# v1_4_button.net
KiCad netlist of a schematic drawn in EAGLE
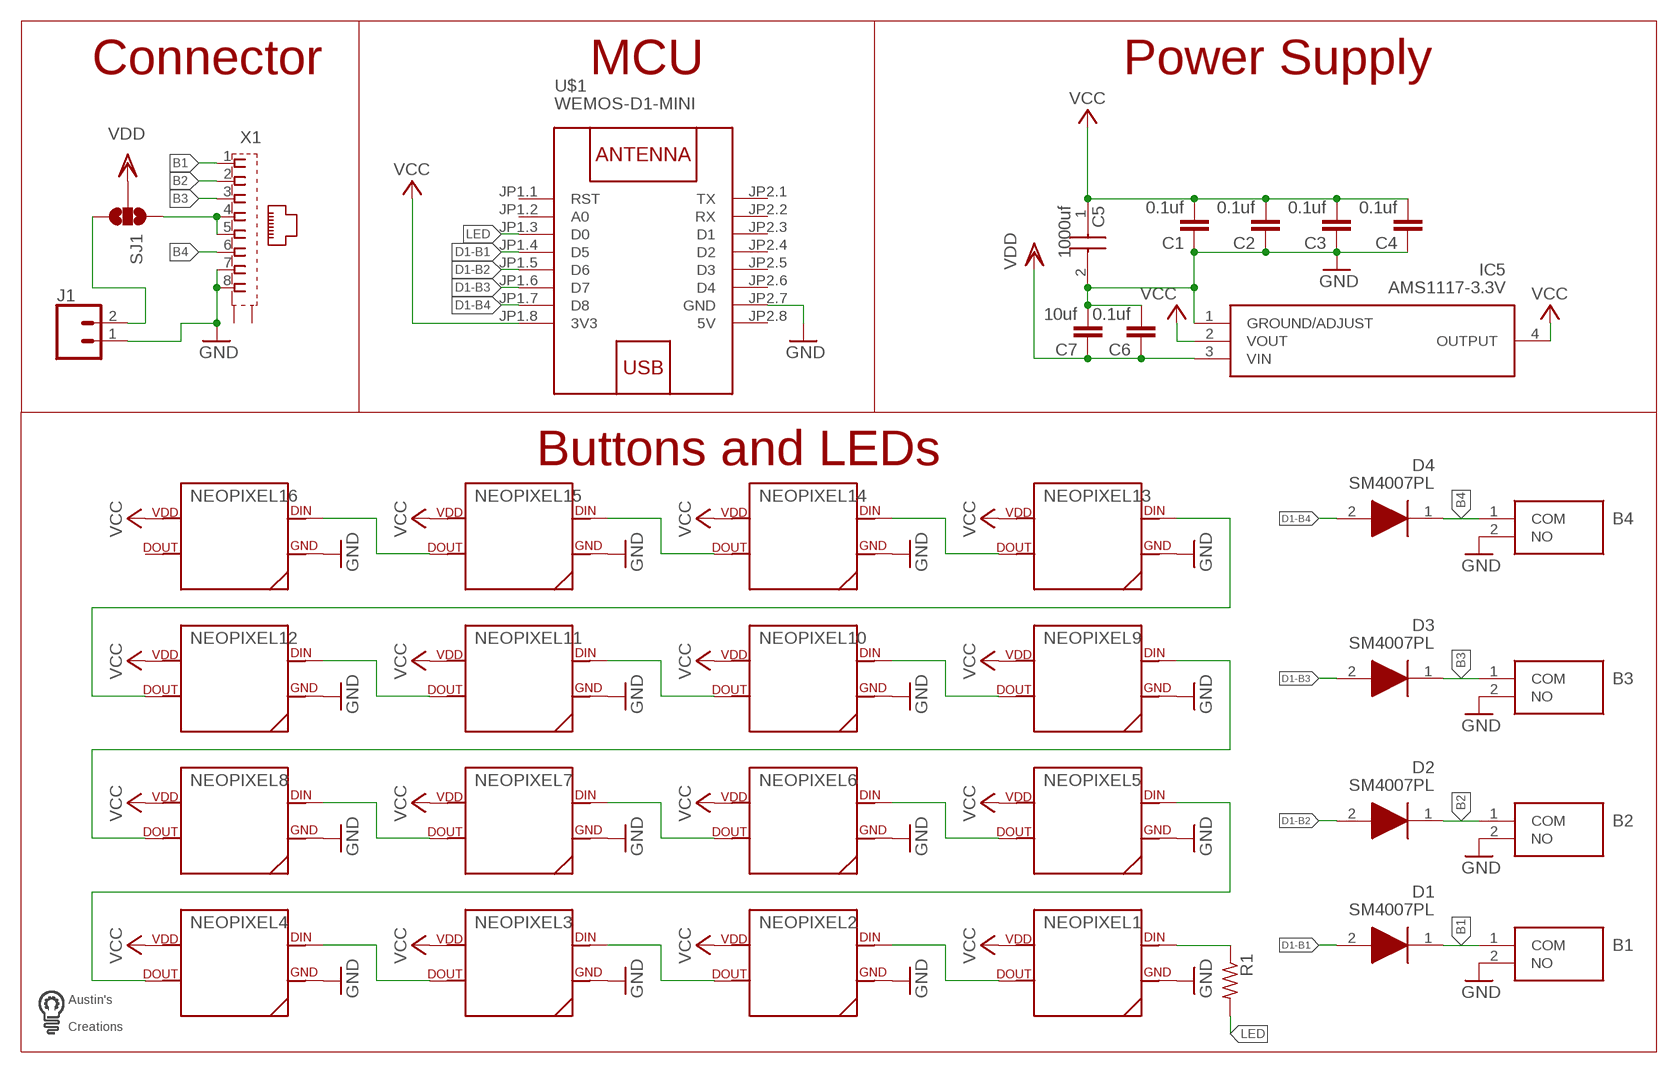
[diagram p0: schematic, sheet 1]

(export (version "E")
  (design (tool "Eeschema 10.0.6"))
  (components
    (comp (ref "B1")
      (value "PTS636_SM25F_SMTR_LFS")
      (footprint "eagle-import:PTS636SM25FSMTRLFS")
      (fields
        (field (name "ARROW_PART_NUMBER") "PTS636 SM25F SMTR LFS")
        (field (name "MOUSER_PART_NUMBER") "611-PTS636SM25FSMTRL")
      )
      (libsource (lib "eagle-import") (part "PTS636_SM25F_SMTR_LFS"))
    )
    (comp (ref "B2")
      (value "PTS636_SM25F_SMTR_LFS")
      (footprint "eagle-import:PTS636SM25FSMTRLFS")
      (fields
        (field (name "ARROW_PART_NUMBER") "PTS636 SM25F SMTR LFS")
        (field (name "MOUSER_PART_NUMBER") "611-PTS636SM25FSMTRL")
      )
      (libsource (lib "eagle-import") (part "PTS636_SM25F_SMTR_LFS"))
    )
    (comp (ref "B3")
      (value "PTS636_SM25F_SMTR_LFS")
      (footprint "eagle-import:PTS636SM25FSMTRLFS")
      (fields
        (field (name "ARROW_PART_NUMBER") "PTS636 SM25F SMTR LFS")
        (field (name "MOUSER_PART_NUMBER") "611-PTS636SM25FSMTRL")
      )
      (libsource (lib "eagle-import") (part "PTS636_SM25F_SMTR_LFS"))
    )
    (comp (ref "B4")
      (value "PTS636_SM25F_SMTR_LFS")
      (footprint "eagle-import:PTS636SM25FSMTRLFS")
      (fields
        (field (name "ARROW_PART_NUMBER") "PTS636 SM25F SMTR LFS")
        (field (name "MOUSER_PART_NUMBER") "611-PTS636SM25FSMTRL")
      )
      (libsource (lib "eagle-import") (part "PTS636_SM25F_SMTR_LFS"))
    )
    (comp (ref "C1")
      (value "0.1uf")
      (footprint "eagle-import:C0603")
      (libsource (lib "eagle-import") (part "C-EUC0603"))
    )
    (comp (ref "C2")
      (value "0.1uf")
      (footprint "eagle-import:C0603")
      (libsource (lib "eagle-import") (part "C-EUC0603"))
    )
    (comp (ref "C3")
      (value "0.1uf")
      (footprint "eagle-import:C0603")
      (libsource (lib "eagle-import") (part "C-EUC0603"))
    )
    (comp (ref "C4")
      (value "0.1uf")
      (footprint "eagle-import:C0603")
      (libsource (lib "eagle-import") (part "C-EUC0603"))
    )
    (comp (ref "C5")
      (value "1000uf")
      (footprint "eagle-import:CAPAE1030X1050N")
      (fields
        (field (name "MANUFACTURER_PART_NUMBER") "EEE-0JA102P")
        (field (name "MOUSER_PART_NUMBER") "667-EEE-0JA102P")
      )
      (libsource (lib "eagle-import") (part "EEE-0JA102P"))
    )
    (comp (ref "C6")
      (value "0.1uf")
      (footprint "eagle-import:C0603")
      (libsource (lib "eagle-import") (part "C-EUC0603"))
    )
    (comp (ref "C7")
      (value "10uf")
      (footprint "eagle-import:C0603")
      (libsource (lib "eagle-import") (part "C-EUC0603"))
    )
    (comp (ref "D1")
      (value "SM4007PL")
      (footprint "eagle-import:SODFL3718X125N")
      (libsource (lib "eagle-import") (part "SM4007PL"))
    )
    (comp (ref "D2")
      (value "SM4007PL")
      (footprint "eagle-import:SODFL3718X125N")
      (libsource (lib "eagle-import") (part "SM4007PL"))
    )
    (comp (ref "D3")
      (value "SM4007PL")
      (footprint "eagle-import:SODFL3718X125N")
      (libsource (lib "eagle-import") (part "SM4007PL"))
    )
    (comp (ref "D4")
      (value "SM4007PL")
      (footprint "eagle-import:SODFL3718X125N")
      (libsource (lib "eagle-import") (part "SM4007PL"))
    )
    (comp (ref "IC5")
      (value "AMS1117-3.3V")
      (footprint "eagle-import:SOT229P700X180-4N")
      (fields (field (name "MANUFACTURER_PART_NUMBER") "ams1117-3.3v"))
      (libsource (lib "eagle-import") (part "AMS1117-3.3V"))
    )
    (comp (ref "J1")
      (value "CONN_025MM")
      (footprint "eagle-import:SCREWTERMINAL-5MM-2")
      (libsource (lib "eagle-import") (part "CONN_025MM"))
    )
    (comp (ref "NEOPIXEL1")
      (value "SK6812NEOPIXEL5050")
      (footprint "eagle-import:SK6812")
      (libsource (lib "eagle-import") (part "SK68125050NEOPIXEL"))
    )
    (comp (ref "NEOPIXEL2")
      (value "SK6812NEOPIXEL5050")
      (footprint "eagle-import:SK6812")
      (libsource (lib "eagle-import") (part "SK68125050NEOPIXEL"))
    )
    (comp (ref "NEOPIXEL3")
      (value "SK6812NEOPIXEL5050")
      (footprint "eagle-import:SK6812")
      (libsource (lib "eagle-import") (part "SK68125050NEOPIXEL"))
    )
    (comp (ref "NEOPIXEL4")
      (value "SK6812NEOPIXEL5050")
      (footprint "eagle-import:SK6812")
      (libsource (lib "eagle-import") (part "SK68125050NEOPIXEL"))
    )
    (comp (ref "NEOPIXEL5")
      (value "SK6812NEOPIXEL5050")
      (footprint "eagle-import:SK6812")
      (libsource (lib "eagle-import") (part "SK68125050NEOPIXEL"))
    )
    (comp (ref "NEOPIXEL6")
      (value "SK6812NEOPIXEL5050")
      (footprint "eagle-import:SK6812")
      (libsource (lib "eagle-import") (part "SK68125050NEOPIXEL"))
    )
    (comp (ref "NEOPIXEL7")
      (value "SK6812NEOPIXEL5050")
      (footprint "eagle-import:SK6812")
      (libsource (lib "eagle-import") (part "SK68125050NEOPIXEL"))
    )
    (comp (ref "NEOPIXEL8")
      (value "SK6812NEOPIXEL5050")
      (footprint "eagle-import:SK6812")
      (libsource (lib "eagle-import") (part "SK68125050NEOPIXEL"))
    )
    (comp (ref "NEOPIXEL9")
      (value "SK6812NEOPIXEL5050")
      (footprint "eagle-import:SK6812")
      (libsource (lib "eagle-import") (part "SK68125050NEOPIXEL"))
    )
    (comp (ref "NEOPIXEL10")
      (value "SK6812NEOPIXEL5050")
      (footprint "eagle-import:SK6812")
      (libsource (lib "eagle-import") (part "SK68125050NEOPIXEL"))
    )
    (comp (ref "NEOPIXEL11")
      (value "SK6812NEOPIXEL5050")
      (footprint "eagle-import:SK6812")
      (libsource (lib "eagle-import") (part "SK68125050NEOPIXEL"))
    )
    (comp (ref "NEOPIXEL12")
      (value "SK6812NEOPIXEL5050")
      (footprint "eagle-import:SK6812")
      (libsource (lib "eagle-import") (part "SK68125050NEOPIXEL"))
    )
    (comp (ref "NEOPIXEL13")
      (value "SK6812NEOPIXEL5050")
      (footprint "eagle-import:SK6812")
      (libsource (lib "eagle-import") (part "SK68125050NEOPIXEL"))
    )
    (comp (ref "NEOPIXEL14")
      (value "SK6812NEOPIXEL5050")
      (footprint "eagle-import:SK6812")
      (libsource (lib "eagle-import") (part "SK68125050NEOPIXEL"))
    )
    (comp (ref "NEOPIXEL15")
      (value "SK6812NEOPIXEL5050")
      (footprint "eagle-import:SK6812")
      (libsource (lib "eagle-import") (part "SK68125050NEOPIXEL"))
    )
    (comp (ref "NEOPIXEL16")
      (value "SK6812NEOPIXEL5050")
      (footprint "eagle-import:SK6812")
      (libsource (lib "eagle-import") (part "SK68125050NEOPIXEL"))
    )
    (comp (ref "R1")
      (value "R-US_R0603")
      (footprint "eagle-import:R0603")
      (libsource (lib "eagle-import") (part "R-US_R0603"))
    )
    (comp (ref "SJ1")
      (value "SOLDERJUMPER_2WAYPASTE1&2")
      (footprint "eagle-import:SJ_3_PASTE1&2")
      (libsource (lib "eagle-import") (part "SOLDERJUMPER_2WAYPASTE1&2"))
    )
    (comp (ref "U$1")
      (value "WEMOS-D1-MINI")
      (footprint "eagle-import:WEMOS-D1-MINI")
      (libsource (lib "eagle-import") (part "WEMOS-D1-MINI"))
    )
    (comp (ref "U$2")
      (value "LOGO")
      (footprint "eagle-import:LOGO")
      (libsource (lib "eagle-import") (part "LOGO"))
    )
    (comp (ref "X1")
      (value "0446200002")
      (footprint "eagle-import:0446200002")
      (fields (field (name "MF") "MOLEX"))
      (libsource (lib "eagle-import") (part "0446200002"))
    )
  )
  (nets
    (net (code "1") (name "/5V") (class "Default")
      (node (ref "U$1") (pin "JP2.8") (pinfunction "5V_JP2.8") (pintype "power_in"))
    )
    (net (code "2") (name "B1") (class "Default")
      (node (ref "B1") (pin "1") (pinfunction "COM_1") (pintype "bidirectional"))
      (node (ref "D1") (pin "1") (pinfunction "K_1") (pintype "bidirectional"))
      (node (ref "X1") (pin "1") (pinfunction "1_1") (pintype "passive"))
    )
    (net (code "3") (name "B2") (class "Default")
      (node (ref "B2") (pin "1") (pinfunction "COM_1") (pintype "bidirectional"))
      (node (ref "D2") (pin "1") (pinfunction "K_1") (pintype "bidirectional"))
      (node (ref "X1") (pin "2") (pinfunction "2_2") (pintype "passive"))
    )
    (net (code "4") (name "B3") (class "Default")
      (node (ref "B3") (pin "1") (pinfunction "COM_1") (pintype "bidirectional"))
      (node (ref "D3") (pin "1") (pinfunction "K_1") (pintype "bidirectional"))
      (node (ref "X1") (pin "3") (pinfunction "3_3") (pintype "passive"))
    )
    (net (code "5") (name "B4") (class "Default")
      (node (ref "B4") (pin "1") (pinfunction "COM_1") (pintype "bidirectional"))
      (node (ref "D4") (pin "1") (pinfunction "K_1") (pintype "bidirectional"))
      (node (ref "X1") (pin "6") (pinfunction "6_6") (pintype "passive"))
    )
    (net (code "6") (name "D1-B1") (class "Default")
      (node (ref "D1") (pin "2") (pinfunction "A_2") (pintype "bidirectional"))
      (node (ref "U$1") (pin "JP1.4") (pinfunction "D5_JP1.4") (pintype "bidirectional"))
    )
    (net (code "7") (name "D1-B2") (class "Default")
      (node (ref "D2") (pin "2") (pinfunction "A_2") (pintype "bidirectional"))
      (node (ref "U$1") (pin "JP1.5") (pinfunction "D6_JP1.5") (pintype "bidirectional"))
    )
    (net (code "8") (name "D1-B3") (class "Default")
      (node (ref "D3") (pin "2") (pinfunction "A_2") (pintype "bidirectional"))
      (node (ref "U$1") (pin "JP1.6") (pinfunction "D7_JP1.6") (pintype "bidirectional"))
    )
    (net (code "9") (name "D1-B4") (class "Default")
      (node (ref "D4") (pin "2") (pinfunction "A_2") (pintype "bidirectional"))
      (node (ref "U$1") (pin "JP1.7") (pinfunction "D8_JP1.7") (pintype "bidirectional"))
    )
    (net (code "10") (name "GND") (class "Default")
      (node (ref "B1") (pin "2") (pinfunction "NO_2") (pintype "bidirectional"))
      (node (ref "B2") (pin "2") (pinfunction "NO_2") (pintype "bidirectional"))
      (node (ref "B3") (pin "2") (pinfunction "NO_2") (pintype "bidirectional"))
      (node (ref "B4") (pin "2") (pinfunction "NO_2") (pintype "bidirectional"))
      (node (ref "C1") (pin "1") (pinfunction "1_1") (pintype "passive"))
      (node (ref "C2") (pin "1") (pinfunction "1_1") (pintype "passive"))
      (node (ref "C3") (pin "1") (pinfunction "1_1") (pintype "passive"))
      (node (ref "C4") (pin "1") (pinfunction "1_1") (pintype "passive"))
      (node (ref "C5") (pin "2") (pinfunction "-_2") (pintype "bidirectional"))
      (node (ref "C6") (pin "2") (pinfunction "2_2") (pintype "passive"))
      (node (ref "C7") (pin "2") (pinfunction "2_2") (pintype "passive"))
      (node (ref "IC5") (pin "1") (pinfunction "GROUND/ADJUST_1") (pintype "bidirectional"))
      (node (ref "J1") (pin "1") (pinfunction "1_1") (pintype "passive"))
      (node (ref "NEOPIXEL1") (pin "3") (pinfunction "GND_3") (pintype "bidirectional"))
      (node (ref "NEOPIXEL10") (pin "3") (pinfunction "GND_3") (pintype "bidirectional"))
      (node (ref "NEOPIXEL11") (pin "3") (pinfunction "GND_3") (pintype "bidirectional"))
      (node (ref "NEOPIXEL12") (pin "3") (pinfunction "GND_3") (pintype "bidirectional"))
      (node (ref "NEOPIXEL13") (pin "3") (pinfunction "GND_3") (pintype "bidirectional"))
      (node (ref "NEOPIXEL14") (pin "3") (pinfunction "GND_3") (pintype "bidirectional"))
      (node (ref "NEOPIXEL15") (pin "3") (pinfunction "GND_3") (pintype "bidirectional"))
      (node (ref "NEOPIXEL16") (pin "3") (pinfunction "GND_3") (pintype "bidirectional"))
      (node (ref "NEOPIXEL2") (pin "3") (pinfunction "GND_3") (pintype "bidirectional"))
      (node (ref "NEOPIXEL3") (pin "3") (pinfunction "GND_3") (pintype "bidirectional"))
      (node (ref "NEOPIXEL4") (pin "3") (pinfunction "GND_3") (pintype "bidirectional"))
      (node (ref "NEOPIXEL5") (pin "3") (pinfunction "GND_3") (pintype "bidirectional"))
      (node (ref "NEOPIXEL6") (pin "3") (pinfunction "GND_3") (pintype "bidirectional"))
      (node (ref "NEOPIXEL7") (pin "3") (pinfunction "GND_3") (pintype "bidirectional"))
      (node (ref "NEOPIXEL8") (pin "3") (pinfunction "GND_3") (pintype "bidirectional"))
      (node (ref "NEOPIXEL9") (pin "3") (pinfunction "GND_3") (pintype "bidirectional"))
      (node (ref "U$1") (pin "JP2.7") (pinfunction "GND_JP2.7") (pintype "power_in"))
      (node (ref "X1") (pin "7") (pinfunction "7_7") (pintype "passive"))
      (node (ref "X1") (pin "8") (pinfunction "8_8") (pintype "passive"))
    )
    (net (code "11") (name "LED") (class "Default")
      (node (ref "R1") (pin "2") (pinfunction "2_2") (pintype "passive"))
      (node (ref "U$1") (pin "JP1.3") (pinfunction "D0_JP1.3") (pintype "bidirectional"))
    )
    (net (code "12") (name "Net-(J1-Pad2)") (class "Default")
      (node (ref "J1") (pin "2") (pinfunction "2_2") (pintype "passive"))
      (node (ref "SJ1") (pin "3") (pinfunction "3_3") (pintype "passive"))
    )
    (net (code "13") (name "Net-(NEOPIXEL1-DIN)") (class "Default")
      (node (ref "NEOPIXEL1") (pin "4") (pinfunction "DIN_4") (pintype "bidirectional"))
      (node (ref "R1") (pin "1") (pinfunction "1_1") (pintype "passive"))
    )
    (net (code "14") (name "Net-(NEOPIXEL1-DOUT)") (class "Default")
      (node (ref "NEOPIXEL1") (pin "2") (pinfunction "DOUT_2") (pintype "bidirectional"))
      (node (ref "NEOPIXEL2") (pin "4") (pinfunction "DIN_4") (pintype "bidirectional"))
    )
    (net (code "15") (name "Net-(NEOPIXEL2-DOUT)") (class "Default")
      (node (ref "NEOPIXEL2") (pin "2") (pinfunction "DOUT_2") (pintype "bidirectional"))
      (node (ref "NEOPIXEL3") (pin "4") (pinfunction "DIN_4") (pintype "bidirectional"))
    )
    (net (code "16") (name "Net-(NEOPIXEL3-DOUT)") (class "Default")
      (node (ref "NEOPIXEL3") (pin "2") (pinfunction "DOUT_2") (pintype "bidirectional"))
      (node (ref "NEOPIXEL4") (pin "4") (pinfunction "DIN_4") (pintype "bidirectional"))
    )
    (net (code "17") (name "Net-(NEOPIXEL4-DOUT)") (class "Default")
      (node (ref "NEOPIXEL4") (pin "2") (pinfunction "DOUT_2") (pintype "bidirectional"))
      (node (ref "NEOPIXEL5") (pin "4") (pinfunction "DIN_4") (pintype "bidirectional"))
    )
    (net (code "18") (name "Net-(NEOPIXEL5-DOUT)") (class "Default")
      (node (ref "NEOPIXEL5") (pin "2") (pinfunction "DOUT_2") (pintype "bidirectional"))
      (node (ref "NEOPIXEL6") (pin "4") (pinfunction "DIN_4") (pintype "bidirectional"))
    )
    (net (code "19") (name "Net-(NEOPIXEL6-DOUT)") (class "Default")
      (node (ref "NEOPIXEL6") (pin "2") (pinfunction "DOUT_2") (pintype "bidirectional"))
      (node (ref "NEOPIXEL7") (pin "4") (pinfunction "DIN_4") (pintype "bidirectional"))
    )
    (net (code "20") (name "Net-(NEOPIXEL7-DOUT)") (class "Default")
      (node (ref "NEOPIXEL7") (pin "2") (pinfunction "DOUT_2") (pintype "bidirectional"))
      (node (ref "NEOPIXEL8") (pin "4") (pinfunction "DIN_4") (pintype "bidirectional"))
    )
    (net (code "21") (name "Net-(NEOPIXEL8-DOUT)") (class "Default")
      (node (ref "NEOPIXEL8") (pin "2") (pinfunction "DOUT_2") (pintype "bidirectional"))
      (node (ref "NEOPIXEL9") (pin "4") (pinfunction "DIN_4") (pintype "bidirectional"))
    )
    (net (code "22") (name "Net-(NEOPIXEL10-DIN)") (class "Default")
      (node (ref "NEOPIXEL10") (pin "4") (pinfunction "DIN_4") (pintype "bidirectional"))
      (node (ref "NEOPIXEL9") (pin "2") (pinfunction "DOUT_2") (pintype "bidirectional"))
    )
    (net (code "23") (name "Net-(NEOPIXEL10-DOUT)") (class "Default")
      (node (ref "NEOPIXEL10") (pin "2") (pinfunction "DOUT_2") (pintype "bidirectional"))
      (node (ref "NEOPIXEL11") (pin "4") (pinfunction "DIN_4") (pintype "bidirectional"))
    )
    (net (code "24") (name "Net-(NEOPIXEL11-DOUT)") (class "Default")
      (node (ref "NEOPIXEL11") (pin "2") (pinfunction "DOUT_2") (pintype "bidirectional"))
      (node (ref "NEOPIXEL12") (pin "4") (pinfunction "DIN_4") (pintype "bidirectional"))
    )
    (net (code "25") (name "Net-(NEOPIXEL12-DOUT)") (class "Default")
      (node (ref "NEOPIXEL12") (pin "2") (pinfunction "DOUT_2") (pintype "bidirectional"))
      (node (ref "NEOPIXEL13") (pin "4") (pinfunction "DIN_4") (pintype "bidirectional"))
    )
    (net (code "26") (name "Net-(NEOPIXEL13-DOUT)") (class "Default")
      (node (ref "NEOPIXEL13") (pin "2") (pinfunction "DOUT_2") (pintype "bidirectional"))
      (node (ref "NEOPIXEL14") (pin "4") (pinfunction "DIN_4") (pintype "bidirectional"))
    )
    (net (code "27") (name "Net-(NEOPIXEL14-DOUT)") (class "Default")
      (node (ref "NEOPIXEL14") (pin "2") (pinfunction "DOUT_2") (pintype "bidirectional"))
      (node (ref "NEOPIXEL15") (pin "4") (pinfunction "DIN_4") (pintype "bidirectional"))
    )
    (net (code "28") (name "Net-(NEOPIXEL15-DOUT)") (class "Default")
      (node (ref "NEOPIXEL15") (pin "2") (pinfunction "DOUT_2") (pintype "bidirectional"))
      (node (ref "NEOPIXEL16") (pin "4") (pinfunction "DIN_4") (pintype "bidirectional"))
    )
    (net (code "29") (name "Net-(SJ1-Pad1)") (class "Default")
      (node (ref "SJ1") (pin "1") (pinfunction "1_1") (pintype "passive"))
      (node (ref "X1") (pin "4") (pinfunction "4_4") (pintype "passive"))
      (node (ref "X1") (pin "5") (pinfunction "5_5") (pintype "passive"))
    )
    (net (code "30") (name "VCC") (class "Default")
      (node (ref "C1") (pin "2") (pinfunction "2_2") (pintype "passive"))
      (node (ref "C2") (pin "2") (pinfunction "2_2") (pintype "passive"))
      (node (ref "C3") (pin "2") (pinfunction "2_2") (pintype "passive"))
      (node (ref "C4") (pin "2") (pinfunction "2_2") (pintype "passive"))
      (node (ref "C5") (pin "1") (pinfunction "+_1") (pintype "bidirectional"))
      (node (ref "IC5") (pin "2") (pinfunction "VOUT_2") (pintype "bidirectional"))
      (node (ref "IC5") (pin "4") (pinfunction "OUTPUT_4") (pintype "bidirectional"))
      (node (ref "NEOPIXEL1") (pin "1") (pinfunction "VDD_1") (pintype "bidirectional"))
      (node (ref "NEOPIXEL10") (pin "1") (pinfunction "VDD_1") (pintype "bidirectional"))
      (node (ref "NEOPIXEL11") (pin "1") (pinfunction "VDD_1") (pintype "bidirectional"))
      (node (ref "NEOPIXEL12") (pin "1") (pinfunction "VDD_1") (pintype "bidirectional"))
      (node (ref "NEOPIXEL13") (pin "1") (pinfunction "VDD_1") (pintype "bidirectional"))
      (node (ref "NEOPIXEL14") (pin "1") (pinfunction "VDD_1") (pintype "bidirectional"))
      (node (ref "NEOPIXEL15") (pin "1") (pinfunction "VDD_1") (pintype "bidirectional"))
      (node (ref "NEOPIXEL16") (pin "1") (pinfunction "VDD_1") (pintype "bidirectional"))
      (node (ref "NEOPIXEL2") (pin "1") (pinfunction "VDD_1") (pintype "bidirectional"))
      (node (ref "NEOPIXEL3") (pin "1") (pinfunction "VDD_1") (pintype "bidirectional"))
      (node (ref "NEOPIXEL4") (pin "1") (pinfunction "VDD_1") (pintype "bidirectional"))
      (node (ref "NEOPIXEL5") (pin "1") (pinfunction "VDD_1") (pintype "bidirectional"))
      (node (ref "NEOPIXEL6") (pin "1") (pinfunction "VDD_1") (pintype "bidirectional"))
      (node (ref "NEOPIXEL7") (pin "1") (pinfunction "VDD_1") (pintype "bidirectional"))
      (node (ref "NEOPIXEL8") (pin "1") (pinfunction "VDD_1") (pintype "bidirectional"))
      (node (ref "NEOPIXEL9") (pin "1") (pinfunction "VDD_1") (pintype "bidirectional"))
      (node (ref "U$1") (pin "JP1.8") (pinfunction "3V3_JP1.8") (pintype "power_in"))
    )
    (net (code "31") (name "VDD") (class "Default")
      (node (ref "C6") (pin "1") (pinfunction "1_1") (pintype "passive"))
      (node (ref "C7") (pin "1") (pinfunction "1_1") (pintype "passive"))
      (node (ref "IC5") (pin "3") (pinfunction "VIN_3") (pintype "bidirectional"))
      (node (ref "SJ1") (pin "2") (pinfunction "2_2") (pintype "passive"))
    )
    (net (code "32") (name "unconnected-(NEOPIXEL16-DOUT-Pad2)") (class "Default")
      (node (ref "NEOPIXEL16") (pin "2") (pinfunction "DOUT_2") (pintype "bidirectional"))
    )
    (net (code "33") (name "unconnected-(U$1-A0-PadJP1.2)") (class "Default")
      (node (ref "U$1") (pin "JP1.2") (pinfunction "A0_JP1.2") (pintype "bidirectional"))
    )
    (net (code "34") (name "unconnected-(U$1-D1-PadJP2.3)") (class "Default")
      (node (ref "U$1") (pin "JP2.3") (pinfunction "D1_JP2.3") (pintype "bidirectional"))
    )
    (net (code "35") (name "unconnected-(U$1-D2-PadJP2.4)") (class "Default")
      (node (ref "U$1") (pin "JP2.4") (pinfunction "D2_JP2.4") (pintype "bidirectional"))
    )
    (net (code "36") (name "unconnected-(U$1-D3-PadJP2.5)") (class "Default")
      (node (ref "U$1") (pin "JP2.5") (pinfunction "D3_JP2.5") (pintype "bidirectional"))
    )
    (net (code "37") (name "unconnected-(U$1-D4-PadJP2.6)") (class "Default")
      (node (ref "U$1") (pin "JP2.6") (pinfunction "D4_JP2.6") (pintype "bidirectional"))
    )
    (net (code "38") (name "unconnected-(U$1-RST-PadJP1.1)") (class "Default")
      (node (ref "U$1") (pin "JP1.1") (pinfunction "RST_JP1.1") (pintype "bidirectional"))
    )
    (net (code "39") (name "unconnected-(U$1-RX-PadJP2.2)") (class "Default")
      (node (ref "U$1") (pin "JP2.2") (pinfunction "RX_JP2.2") (pintype "bidirectional"))
    )
    (net (code "40") (name "unconnected-(U$1-TX-PadJP2.1)") (class "Default")
      (node (ref "U$1") (pin "JP2.1") (pinfunction "TX_JP2.1") (pintype "bidirectional"))
    )
    (net (code "41") (name "unconnected-(X1-S1-PadS@1)") (class "Default")
      (node (ref "X1") (pin "S@1") (pinfunction "S1_S@1") (pintype "passive"))
    )
    (net (code "42") (name "unconnected-(X1-S2-PadS@2)") (class "Default")
      (node (ref "X1") (pin "S@2") (pinfunction "S2_S@2") (pintype "passive"))
    )
  )
)
